# sdram.net
KiCad netlist of a schematic drawn in Altium Designer
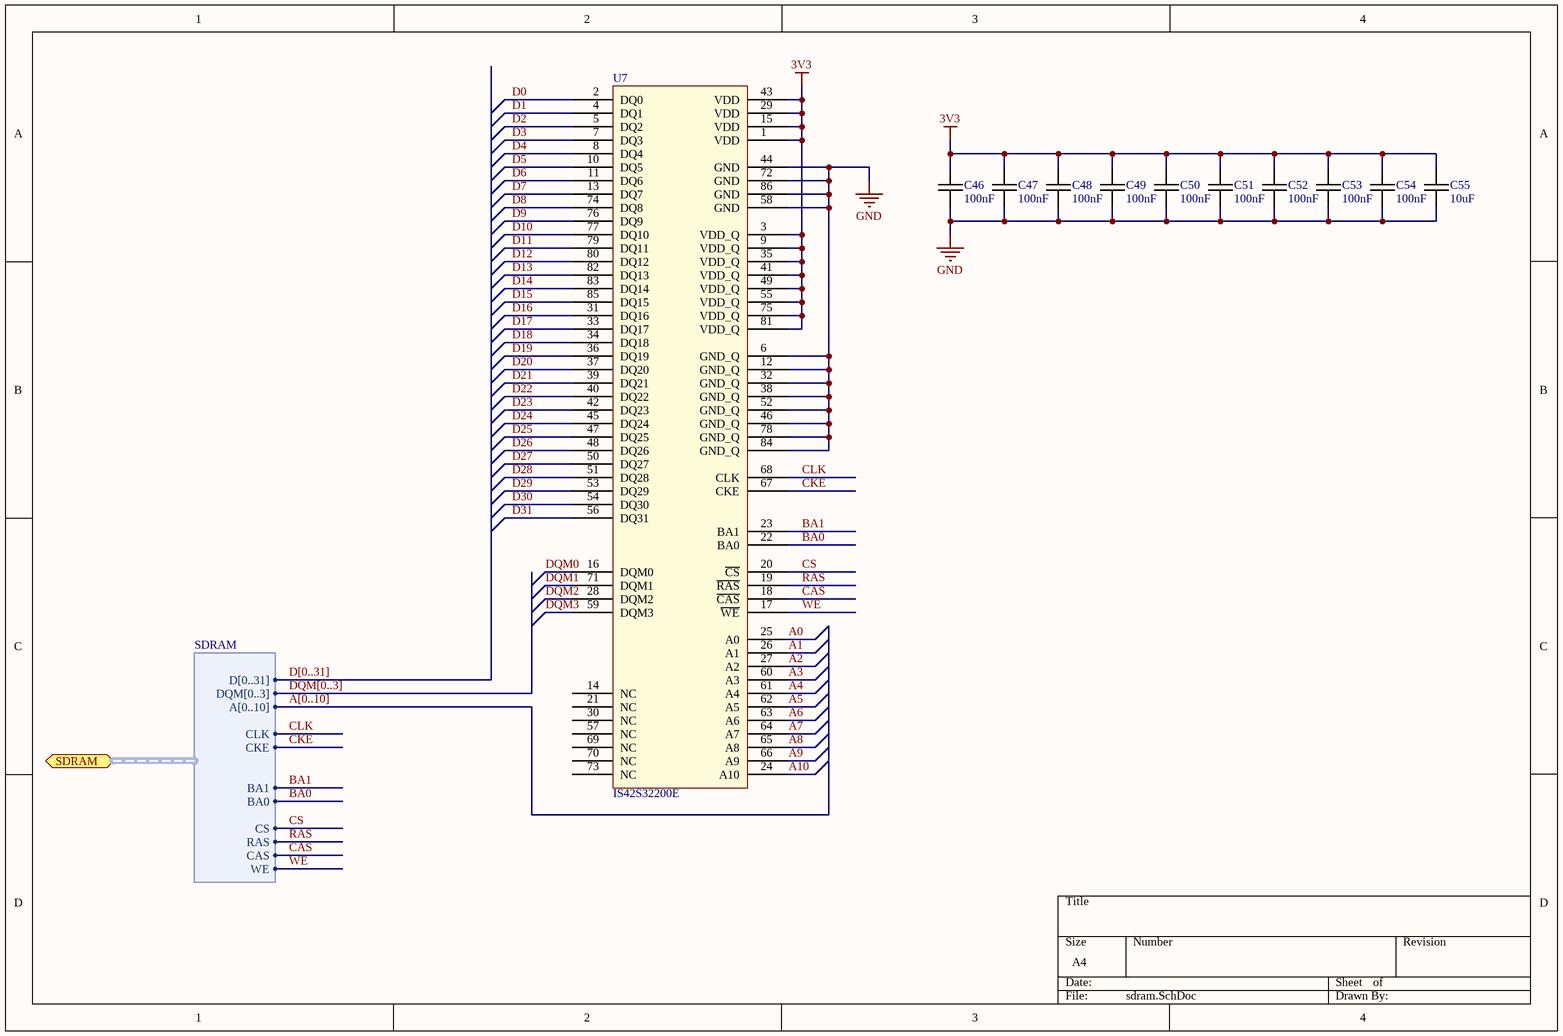
[diagram p0: sdram.SchDoc]

(export (version "E")
  (design (tool "Eeschema 10.0.6"))
  (components
    (comp (ref "C46")
      (value "100nF")
      (footprint "0603C-GENERIC")
      (description "GENERIC CAPACITOR NON POLARISED 0603")
      (fields (field (name "TOLERANCE") "±10%") (field (name "MANUFACTURER PART NUMBER") "C1608X7R1H103K"))
      (libsource (lib "vh_Altium Library") (part "0603C-100NF-50V-X7R-TDK"))
    )
    (comp (ref "C47")
      (value "100nF")
      (footprint "0603C-GENERIC")
      (description "GENERIC CAPACITOR NON POLARISED 0603")
      (fields (field (name "TOLERANCE") "±10%") (field (name "MANUFACTURER PART NUMBER") "C1608X7R1H103K"))
      (libsource (lib "vh_Altium Library") (part "0603C-100NF-50V-X7R-TDK"))
    )
    (comp (ref "C48")
      (value "100nF")
      (footprint "0603C-GENERIC")
      (description "GENERIC CAPACITOR NON POLARISED 0603")
      (fields (field (name "TOLERANCE") "±10%") (field (name "MANUFACTURER PART NUMBER") "C1608X7R1H103K"))
      (libsource (lib "vh_Altium Library") (part "0603C-100NF-50V-X7R-TDK"))
    )
    (comp (ref "C49")
      (value "100nF")
      (footprint "0603C-GENERIC")
      (description "GENERIC CAPACITOR NON POLARISED 0603")
      (fields (field (name "TOLERANCE") "±10%") (field (name "MANUFACTURER PART NUMBER") "C1608X7R1H103K"))
      (libsource (lib "vh_Altium Library") (part "0603C-100NF-50V-X7R-TDK"))
    )
    (comp (ref "C50")
      (value "100nF")
      (footprint "0603C-GENERIC")
      (description "GENERIC CAPACITOR NON POLARISED 0603")
      (fields (field (name "TOLERANCE") "±10%") (field (name "MANUFACTURER PART NUMBER") "C1608X7R1H103K"))
      (libsource (lib "vh_Altium Library") (part "0603C-100NF-50V-X7R-TDK"))
    )
    (comp (ref "C51")
      (value "100nF")
      (footprint "0603C-GENERIC")
      (description "GENERIC CAPACITOR NON POLARISED 0603")
      (fields (field (name "TOLERANCE") "±10%") (field (name "MANUFACTURER PART NUMBER") "C1608X7R1H103K"))
      (libsource (lib "vh_Altium Library") (part "0603C-100NF-50V-X7R-TDK"))
    )
    (comp (ref "C52")
      (value "100nF")
      (footprint "0603C-GENERIC")
      (description "GENERIC CAPACITOR NON POLARISED 0603")
      (fields (field (name "TOLERANCE") "±10%") (field (name "MANUFACTURER PART NUMBER") "C1608X7R1H103K"))
      (libsource (lib "vh_Altium Library") (part "0603C-100NF-50V-X7R-TDK"))
    )
    (comp (ref "C53")
      (value "100nF")
      (footprint "0603C-GENERIC")
      (description "GENERIC CAPACITOR NON POLARISED 0603")
      (fields (field (name "TOLERANCE") "±10%") (field (name "MANUFACTURER PART NUMBER") "C1608X7R1H103K"))
      (libsource (lib "vh_Altium Library") (part "0603C-100NF-50V-X7R-TDK"))
    )
    (comp (ref "C54")
      (value "100nF")
      (footprint "0603C-GENERIC")
      (description "GENERIC CAPACITOR NON POLARISED 0603")
      (fields (field (name "TOLERANCE") "±10%") (field (name "MANUFACTURER PART NUMBER") "C1608X7R1H103K"))
      (libsource (lib "vh_Altium Library") (part "0603C-100NF-50V-X7R-TDK"))
    )
    (comp (ref "C55")
      (value "10uF")
      (footprint "0805C-GENERIC")
      (description "CAPACITOR 0805 CERAMIC")
      (fields
        (field (name "MANUFACTURER PART NUMBER") "C2012X5R1C106M")
        (field (name "MANUFACTURER") "TDK Corporation")
      )
      (libsource (lib "vh_Altium Library") (part "0805C-10UF-16V-X5R-TDK"))
    )
    (comp (ref "U7")
      (value "IS42S32200E")
      (footprint "TSSOP50P1175-86M")
      (libsource (lib "camera_board") (part "IS42S32200E"))
    )
  )
  (nets
    (net (code "2") (name "/A0") (class "Default")
      (node (ref "U7") (pin "25") (pinfunction "A0_25") (pintype "passive"))
    )
    (net (code "3") (name "/A1") (class "Default")
      (node (ref "U7") (pin "26") (pinfunction "A1_26") (pintype "passive"))
    )
    (net (code "4") (name "/A2") (class "Default")
      (node (ref "U7") (pin "27") (pinfunction "A2_27") (pintype "passive"))
    )
    (net (code "5") (name "/A3") (class "Default")
      (node (ref "U7") (pin "60") (pinfunction "A3_60") (pintype "passive"))
    )
    (net (code "6") (name "/A4") (class "Default")
      (node (ref "U7") (pin "61") (pinfunction "A4_61") (pintype "passive"))
    )
    (net (code "7") (name "/A5") (class "Default")
      (node (ref "U7") (pin "62") (pinfunction "A5_62") (pintype "passive"))
    )
    (net (code "8") (name "/A6") (class "Default")
      (node (ref "U7") (pin "63") (pinfunction "A6_63") (pintype "passive"))
    )
    (net (code "9") (name "/A7") (class "Default")
      (node (ref "U7") (pin "64") (pinfunction "A7_64") (pintype "passive"))
    )
    (net (code "10") (name "/A8") (class "Default")
      (node (ref "U7") (pin "65") (pinfunction "A8_65") (pintype "passive"))
    )
    (net (code "11") (name "/A9") (class "Default")
      (node (ref "U7") (pin "66") (pinfunction "A9_66") (pintype "passive"))
    )
    (net (code "12") (name "/A10") (class "Default")
      (node (ref "U7") (pin "24") (pinfunction "A10_24") (pintype "passive"))
    )
    (net (code "13") (name "/BA0") (class "Default")
      (node (ref "U7") (pin "22") (pinfunction "BA0_22") (pintype "passive"))
    )
    (net (code "14") (name "/BA1") (class "Default")
      (node (ref "U7") (pin "23") (pinfunction "BA1_23") (pintype "passive"))
    )
    (net (code "15") (name "/CAS") (class "Default")
      (node (ref "U7") (pin "18") (pinfunction "~{CAS}_18") (pintype "passive"))
    )
    (net (code "16") (name "/CKE") (class "Default")
      (node (ref "U7") (pin "67") (pinfunction "CKE_67") (pintype "passive"))
    )
    (net (code "17") (name "/CLK") (class "Default")
      (node (ref "U7") (pin "68") (pinfunction "CLK_68") (pintype "passive"))
    )
    (net (code "18") (name "/CS") (class "Default")
      (node (ref "U7") (pin "20") (pinfunction "~{CS}_20") (pintype "passive"))
    )
    (net (code "19") (name "/D0") (class "Default")
      (node (ref "U7") (pin "2") (pinfunction "DQ0_2") (pintype "passive"))
    )
    (net (code "20") (name "/D1") (class "Default")
      (node (ref "U7") (pin "4") (pinfunction "DQ1_4") (pintype "passive"))
    )
    (net (code "21") (name "/D2") (class "Default")
      (node (ref "U7") (pin "5") (pinfunction "DQ2_5") (pintype "passive"))
    )
    (net (code "22") (name "/D3") (class "Default")
      (node (ref "U7") (pin "7") (pinfunction "DQ3_7") (pintype "passive"))
    )
    (net (code "23") (name "/D4") (class "Default")
      (node (ref "U7") (pin "8") (pinfunction "DQ4_8") (pintype "passive"))
    )
    (net (code "24") (name "/D5") (class "Default")
      (node (ref "U7") (pin "10") (pinfunction "DQ5_10") (pintype "passive"))
    )
    (net (code "25") (name "/D6") (class "Default")
      (node (ref "U7") (pin "11") (pinfunction "DQ6_11") (pintype "passive"))
    )
    (net (code "26") (name "/D7") (class "Default")
      (node (ref "U7") (pin "13") (pinfunction "DQ7_13") (pintype "passive"))
    )
    (net (code "27") (name "/D8") (class "Default")
      (node (ref "U7") (pin "74") (pinfunction "DQ8_74") (pintype "passive"))
    )
    (net (code "28") (name "/D9") (class "Default")
      (node (ref "U7") (pin "76") (pinfunction "DQ9_76") (pintype "passive"))
    )
    (net (code "29") (name "/D10") (class "Default")
      (node (ref "U7") (pin "77") (pinfunction "DQ10_77") (pintype "passive"))
    )
    (net (code "30") (name "/D11") (class "Default")
      (node (ref "U7") (pin "79") (pinfunction "DQ11_79") (pintype "passive"))
    )
    (net (code "31") (name "/D12") (class "Default")
      (node (ref "U7") (pin "80") (pinfunction "DQ12_80") (pintype "passive"))
    )
    (net (code "32") (name "/D13") (class "Default")
      (node (ref "U7") (pin "82") (pinfunction "DQ13_82") (pintype "passive"))
    )
    (net (code "33") (name "/D14") (class "Default")
      (node (ref "U7") (pin "83") (pinfunction "DQ14_83") (pintype "passive"))
    )
    (net (code "34") (name "/D15") (class "Default")
      (node (ref "U7") (pin "85") (pinfunction "DQ15_85") (pintype "passive"))
    )
    (net (code "35") (name "/D16") (class "Default")
      (node (ref "U7") (pin "31") (pinfunction "DQ16_31") (pintype "passive"))
    )
    (net (code "36") (name "/D17") (class "Default")
      (node (ref "U7") (pin "33") (pinfunction "DQ17_33") (pintype "passive"))
    )
    (net (code "37") (name "/D18") (class "Default")
      (node (ref "U7") (pin "34") (pinfunction "DQ18_34") (pintype "passive"))
    )
    (net (code "38") (name "/D19") (class "Default")
      (node (ref "U7") (pin "36") (pinfunction "DQ19_36") (pintype "passive"))
    )
    (net (code "39") (name "/D20") (class "Default")
      (node (ref "U7") (pin "37") (pinfunction "DQ20_37") (pintype "passive"))
    )
    (net (code "40") (name "/D21") (class "Default")
      (node (ref "U7") (pin "39") (pinfunction "DQ21_39") (pintype "passive"))
    )
    (net (code "41") (name "/D22") (class "Default")
      (node (ref "U7") (pin "40") (pinfunction "DQ22_40") (pintype "passive"))
    )
    (net (code "42") (name "/D23") (class "Default")
      (node (ref "U7") (pin "42") (pinfunction "DQ23_42") (pintype "passive"))
    )
    (net (code "43") (name "/D24") (class "Default")
      (node (ref "U7") (pin "45") (pinfunction "DQ24_45") (pintype "passive"))
    )
    (net (code "44") (name "/D25") (class "Default")
      (node (ref "U7") (pin "47") (pinfunction "DQ25_47") (pintype "passive"))
    )
    (net (code "45") (name "/D26") (class "Default")
      (node (ref "U7") (pin "48") (pinfunction "DQ26_48") (pintype "passive"))
    )
    (net (code "46") (name "/D27") (class "Default")
      (node (ref "U7") (pin "50") (pinfunction "DQ27_50") (pintype "passive"))
    )
    (net (code "47") (name "/D28") (class "Default")
      (node (ref "U7") (pin "51") (pinfunction "DQ28_51") (pintype "passive"))
    )
    (net (code "48") (name "/D29") (class "Default")
      (node (ref "U7") (pin "53") (pinfunction "DQ29_53") (pintype "passive"))
    )
    (net (code "49") (name "/D30") (class "Default")
      (node (ref "U7") (pin "54") (pinfunction "DQ30_54") (pintype "passive"))
    )
    (net (code "50") (name "/D31") (class "Default")
      (node (ref "U7") (pin "56") (pinfunction "DQ31_56") (pintype "passive"))
    )
    (net (code "51") (name "/DQM0") (class "Default")
      (node (ref "U7") (pin "16") (pinfunction "DQM0_16") (pintype "passive"))
    )
    (net (code "52") (name "/DQM1") (class "Default")
      (node (ref "U7") (pin "71") (pinfunction "DQM1_71") (pintype "passive"))
    )
    (net (code "53") (name "/DQM2") (class "Default")
      (node (ref "U7") (pin "28") (pinfunction "DQM2_28") (pintype "passive"))
    )
    (net (code "54") (name "/DQM3") (class "Default")
      (node (ref "U7") (pin "59") (pinfunction "DQM3_59") (pintype "passive"))
    )
    (net (code "57") (name "/RAS") (class "Default")
      (node (ref "U7") (pin "19") (pinfunction "~{RAS}_19") (pintype "passive"))
    )
    (net (code "59") (name "/WE") (class "Default")
      (node (ref "U7") (pin "17") (pinfunction "~{WE}_17") (pintype "passive"))
    )
    (net (code "61") (name "3V3") (class "Default")
      (node (ref "C46") (pin "1") (pintype "passive"))
      (node (ref "C47") (pin "1") (pintype "passive"))
      (node (ref "C48") (pin "1") (pintype "passive"))
      (node (ref "C49") (pin "1") (pintype "passive"))
      (node (ref "C50") (pin "1") (pintype "passive"))
      (node (ref "C51") (pin "1") (pintype "passive"))
      (node (ref "C52") (pin "1") (pintype "passive"))
      (node (ref "C53") (pin "1") (pintype "passive"))
      (node (ref "C54") (pin "1") (pintype "passive"))
      (node (ref "C55") (pin "1") (pintype "passive"))
      (node (ref "U7") (pin "1") (pinfunction "VDD_1") (pintype "passive"))
      (node (ref "U7") (pin "15") (pinfunction "VDD_15") (pintype "passive"))
      (node (ref "U7") (pin "29") (pinfunction "VDD_29") (pintype "passive"))
      (node (ref "U7") (pin "3") (pinfunction "VDD_Q_3") (pintype "passive"))
      (node (ref "U7") (pin "35") (pinfunction "VDD_Q_35") (pintype "passive"))
      (node (ref "U7") (pin "41") (pinfunction "VDD_Q_41") (pintype "passive"))
      (node (ref "U7") (pin "43") (pinfunction "VDD_43") (pintype "passive"))
      (node (ref "U7") (pin "49") (pinfunction "VDD_Q_49") (pintype "passive"))
      (node (ref "U7") (pin "55") (pinfunction "VDD_Q_55") (pintype "passive"))
      (node (ref "U7") (pin "75") (pinfunction "VDD_Q_75") (pintype "passive"))
      (node (ref "U7") (pin "81") (pinfunction "VDD_Q_81") (pintype "passive"))
      (node (ref "U7") (pin "9") (pinfunction "VDD_Q_9") (pintype "passive"))
    )
    (net (code "62") (name "GND") (class "Default")
      (node (ref "C46") (pin "2") (pintype "passive"))
      (node (ref "C47") (pin "2") (pintype "passive"))
      (node (ref "C48") (pin "2") (pintype "passive"))
      (node (ref "C49") (pin "2") (pintype "passive"))
      (node (ref "C50") (pin "2") (pintype "passive"))
      (node (ref "C51") (pin "2") (pintype "passive"))
      (node (ref "C52") (pin "2") (pintype "passive"))
      (node (ref "C53") (pin "2") (pintype "passive"))
      (node (ref "C54") (pin "2") (pintype "passive"))
      (node (ref "C55") (pin "2") (pintype "passive"))
      (node (ref "U7") (pin "12") (pinfunction "GND_Q_12") (pintype "passive"))
      (node (ref "U7") (pin "32") (pinfunction "GND_Q_32") (pintype "passive"))
      (node (ref "U7") (pin "38") (pinfunction "GND_Q_38") (pintype "passive"))
      (node (ref "U7") (pin "44") (pinfunction "GND_44") (pintype "passive"))
      (node (ref "U7") (pin "46") (pinfunction "GND_Q_46") (pintype "passive"))
      (node (ref "U7") (pin "52") (pinfunction "GND_Q_52") (pintype "passive"))
      (node (ref "U7") (pin "58") (pinfunction "GND_58") (pintype "passive"))
      (node (ref "U7") (pin "6") (pinfunction "GND_Q_6") (pintype "passive"))
      (node (ref "U7") (pin "72") (pinfunction "GND_72") (pintype "passive"))
      (node (ref "U7") (pin "78") (pinfunction "GND_Q_78") (pintype "passive"))
      (node (ref "U7") (pin "84") (pinfunction "GND_Q_84") (pintype "passive"))
      (node (ref "U7") (pin "86") (pinfunction "GND_86") (pintype "passive"))
    )
    (net (code "63") (name "unconnected-(U7-NC-Pad14)") (class "Default")
      (node (ref "U7") (pin "14") (pinfunction "NC_14") (pintype "passive"))
    )
    (net (code "64") (name "unconnected-(U7-NC-Pad21)") (class "Default")
      (node (ref "U7") (pin "21") (pinfunction "NC_21") (pintype "passive"))
    )
    (net (code "65") (name "unconnected-(U7-NC-Pad30)") (class "Default")
      (node (ref "U7") (pin "30") (pinfunction "NC_30") (pintype "passive"))
    )
    (net (code "66") (name "unconnected-(U7-NC-Pad57)") (class "Default")
      (node (ref "U7") (pin "57") (pinfunction "NC_57") (pintype "passive"))
    )
    (net (code "67") (name "unconnected-(U7-NC-Pad69)") (class "Default")
      (node (ref "U7") (pin "69") (pinfunction "NC_69") (pintype "passive"))
    )
    (net (code "68") (name "unconnected-(U7-NC-Pad70)") (class "Default")
      (node (ref "U7") (pin "70") (pinfunction "NC_70") (pintype "passive"))
    )
    (net (code "69") (name "unconnected-(U7-NC-Pad73)") (class "Default")
      (node (ref "U7") (pin "73") (pinfunction "NC_73") (pintype "passive"))
    )
  )
)
